# Sound_Board.net
KiCad netlist of a schematic drawn in Altium Designer
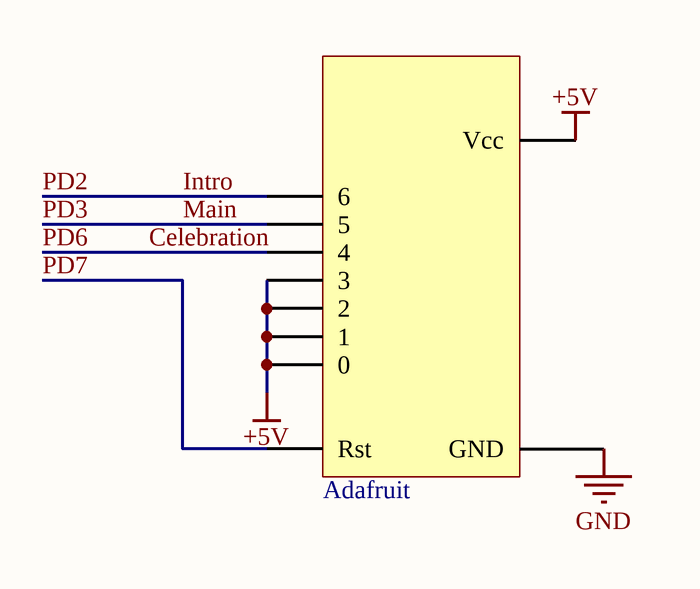
[diagram p0: Sound Board.SchDoc]

(export (version "E")
  (design (tool "Eeschema 10.0.6"))
  (components
    (comp (ref "A1")
      (value "Adafruit")
      (footprint "DIP-16/X1.5")
      (description "8-Bit Serial-Input/Serial or Prallel-Output Shift Register with Latched 3-State Outputs")
      (fields
        (field (name "MANUFACTURER") "ON Semiconductor")
        (field (name "PUBLISHER") "Altium Hobart Technology Centre")
      )
      (libsource (lib "ME218_BaseLib") (part "74xxx595"))
    )
  )
  (nets
    (net (code "1") (name "+5V") (class "Default")
      (node (ref "A1") (pin "1") (pinfunction "0_1") (pintype "passive"))
      (node (ref "A1") (pin "14") (pinfunction "Vcc_14") (pintype "passive"))
      (node (ref "A1") (pin "2") (pinfunction "1_2") (pintype "passive"))
      (node (ref "A1") (pin "3") (pinfunction "2_3") (pintype "passive"))
      (node (ref "A1") (pin "4") (pinfunction "3_4") (pintype "passive"))
    )
    (net (code "2") (name "/Celebration") (class "Default")
      (node (ref "A1") (pin "5") (pinfunction "4_5") (pintype "passive"))
    )
    (net (code "3") (name "/Intro") (class "Default")
      (node (ref "A1") (pin "7") (pinfunction "6_7") (pintype "passive"))
    )
    (net (code "4") (name "/Main") (class "Default")
      (node (ref "A1") (pin "6") (pinfunction "5_6") (pintype "passive"))
    )
    (net (code "5") (name "/PD7") (class "Default")
      (node (ref "A1") (pin "16") (pinfunction "Rst_16") (pintype "passive"))
    )
    (net (code "6") (name "GND") (class "Default")
      (node (ref "A1") (pin "0") (pinfunction "GND_0") (pintype "passive"))
    )
  )
)
